# rpi-cc2538-uart.net
KiCad netlist of a schematic drawn in EAGLE
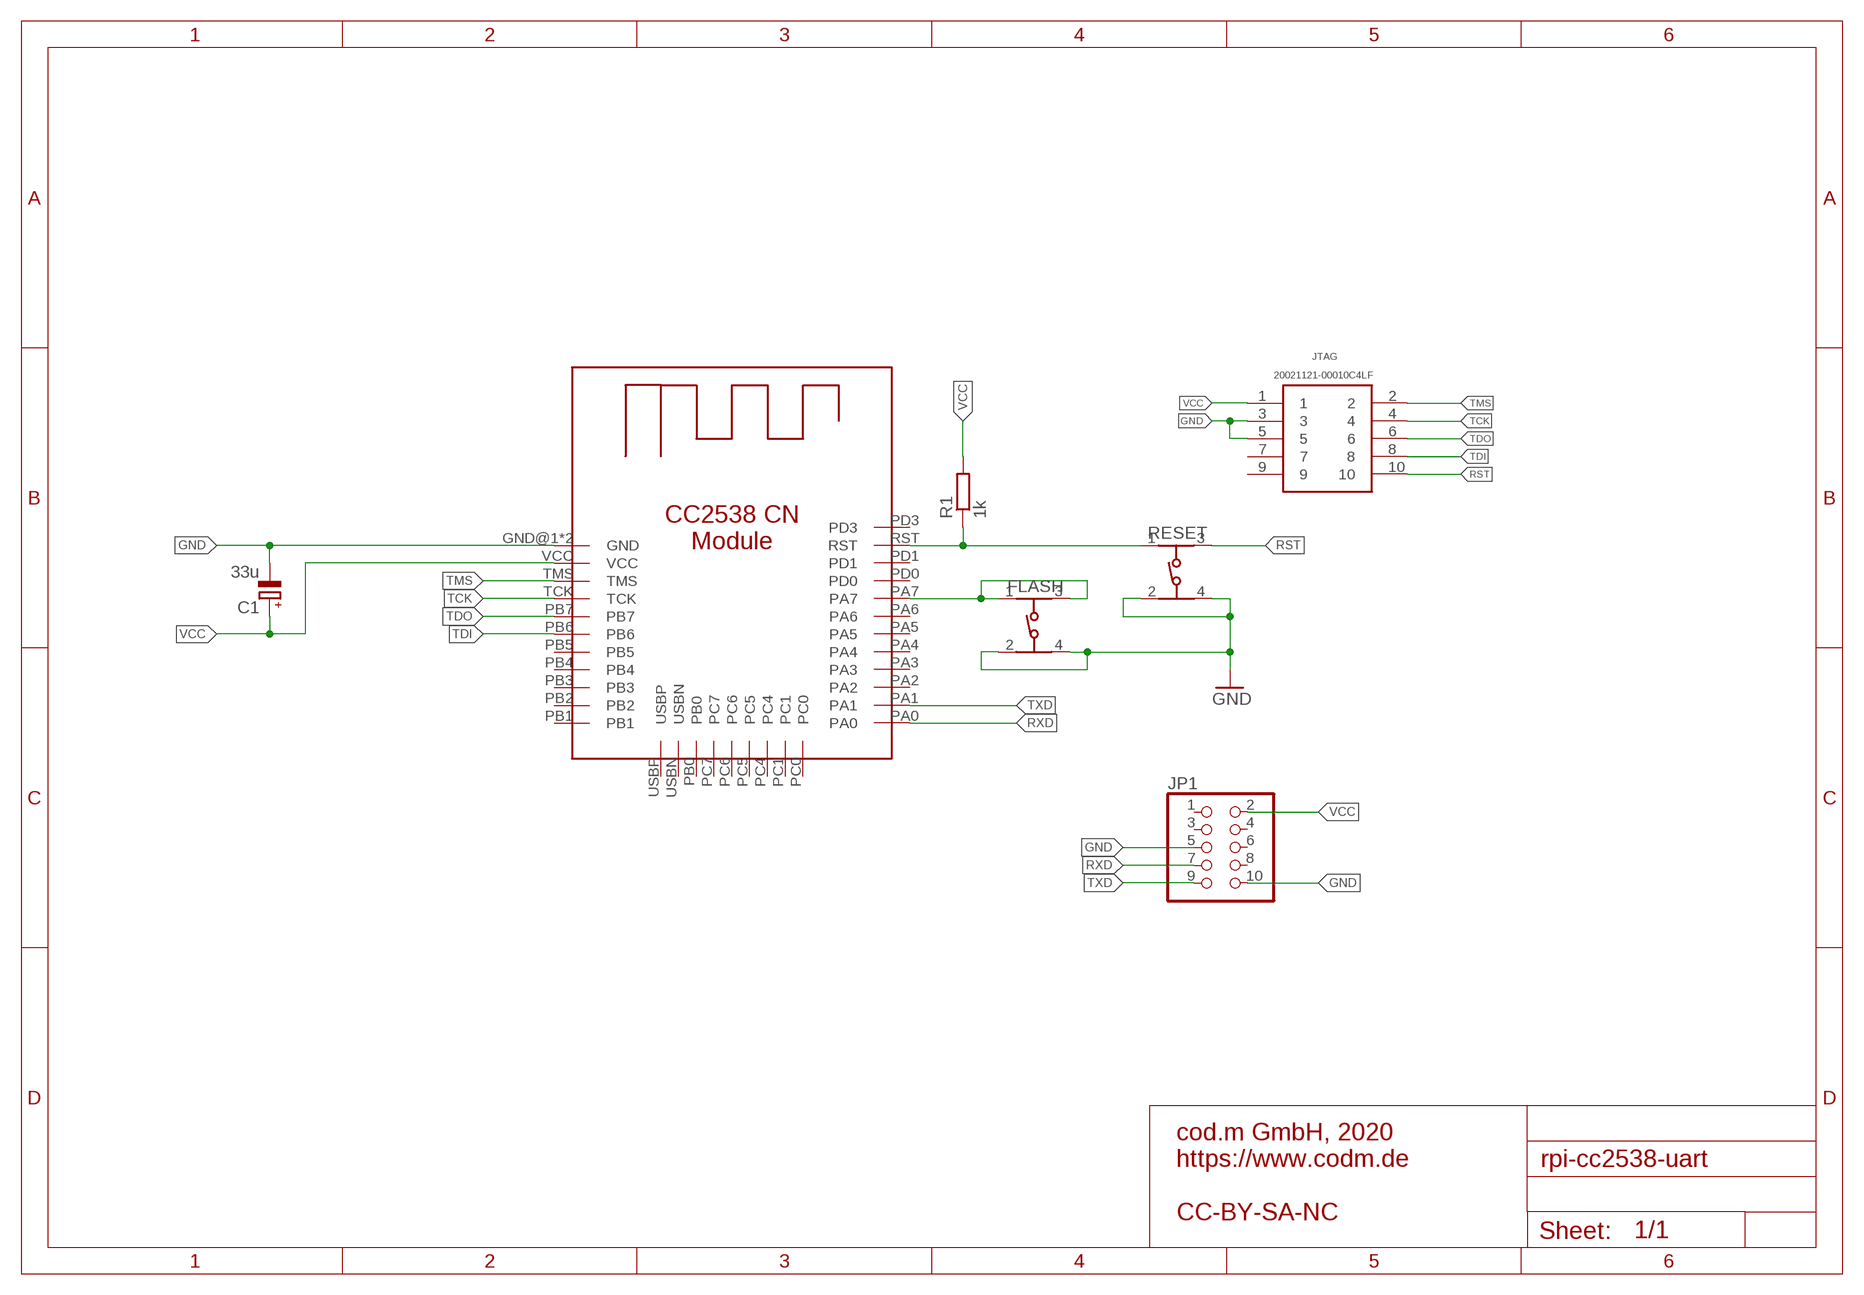
[diagram p0: schematic, sheet 1]

(export (version "E")
  (design (tool "Eeschema 10.0.6"))
  (components
    (comp (ref "C1")
      (value "33u")
      (footprint "eagle-import:A_3216-18W")
      (libsource (lib "eagle-import") (part "CPOL-EUA/3216-18W"))
    )
    (comp (ref "FLASH")
      (value "434153017835")
      (footprint "eagle-import:434153017835")
      (libsource (lib "eagle-import") (part "434153017835"))
    )
    (comp (ref "JP1")
      (value "PINHD-2X5")
      (footprint "eagle-import:2X05")
      (libsource (lib "eagle-import") (part "PINHD-2X5"))
    )
    (comp (ref "JTAG")
      (value "20021121-00010C4LF")
      (footprint "eagle-import:2002112100010C4LF")
      (fields (field (name "MOUSER_PART_NUMBER") "649-202112100010C4LF"))
      (libsource (lib "eagle-import") (part "20021121-00010C4LF"))
    )
    (comp (ref "R1")
      (value "1k")
      (footprint "eagle-import:R0805")
      (libsource (lib "eagle-import") (part "R-EU_R0805"))
    )
    (comp (ref "RESET")
      (value "434153017835")
      (footprint "eagle-import:434153017835")
      (libsource (lib "eagle-import") (part "434153017835"))
    )
    (comp (ref "U$1")
      (value "CC2538-CN")
      (footprint "eagle-import:CC2538-CN")
      (libsource (lib "eagle-import") (part "CC2538-CN"))
    )
  )
  (nets
    (net (code "1") (name "GND") (class "Default")
      (node (ref "C1") (pin "-") (pinfunction "-_-") (pintype "passive"))
      (node (ref "FLASH") (pin "2") (pinfunction "3_2") (pintype "passive"))
      (node (ref "FLASH") (pin "4") (pinfunction "4_4") (pintype "passive"))
      (node (ref "JP1") (pin "10") (pinfunction "10_10") (pintype "passive"))
      (node (ref "JP1") (pin "5") (pinfunction "5_5") (pintype "passive"))
      (node (ref "JTAG") (pin "3") (pinfunction "3_3") (pintype "bidirectional"))
      (node (ref "JTAG") (pin "5") (pinfunction "5_5") (pintype "bidirectional"))
      (node (ref "RESET") (pin "2") (pinfunction "3_2") (pintype "passive"))
      (node (ref "RESET") (pin "4") (pinfunction "4_4") (pintype "passive"))
      (node (ref "U$1") (pin "GND@1") (pinfunction "GND_GND@1") (pintype "bidirectional"))
      (node (ref "U$1") (pin "GND@2") (pinfunction "GND_GND@2") (pintype "bidirectional"))
    )
    (net (code "2") (name "Net-(FLASH-2)") (class "Default")
      (node (ref "FLASH") (pin "1") (pinfunction "1_1") (pintype "passive"))
      (node (ref "FLASH") (pin "3") (pinfunction "2_3") (pintype "passive"))
      (node (ref "U$1") (pin "PA7") (pinfunction "PA7_PA7") (pintype "bidirectional"))
    )
    (net (code "3") (name "RST") (class "Default")
      (node (ref "JTAG") (pin "10") (pinfunction "10_10") (pintype "bidirectional"))
      (node (ref "R1") (pin "1") (pinfunction "1_1") (pintype "passive"))
      (node (ref "RESET") (pin "1") (pinfunction "1_1") (pintype "passive"))
      (node (ref "RESET") (pin "3") (pinfunction "2_3") (pintype "passive"))
      (node (ref "U$1") (pin "RST") (pinfunction "RST_RST") (pintype "bidirectional"))
    )
    (net (code "4") (name "RXD") (class "Default")
      (node (ref "JP1") (pin "7") (pinfunction "7_7") (pintype "passive"))
      (node (ref "U$1") (pin "PA0") (pinfunction "PA0_PA0") (pintype "bidirectional"))
    )
    (net (code "5") (name "TCK") (class "Default")
      (node (ref "JTAG") (pin "4") (pinfunction "4_4") (pintype "bidirectional"))
      (node (ref "U$1") (pin "TCK") (pinfunction "TCK_TCK") (pintype "bidirectional"))
    )
    (net (code "6") (name "TDI") (class "Default")
      (node (ref "JTAG") (pin "8") (pinfunction "8_8") (pintype "bidirectional"))
      (node (ref "U$1") (pin "PB6") (pinfunction "PB6_PB6") (pintype "bidirectional"))
    )
    (net (code "7") (name "TDO") (class "Default")
      (node (ref "JTAG") (pin "6") (pinfunction "6_6") (pintype "bidirectional"))
      (node (ref "U$1") (pin "PB7") (pinfunction "PB7_PB7") (pintype "bidirectional"))
    )
    (net (code "8") (name "TMS") (class "Default")
      (node (ref "JTAG") (pin "2") (pinfunction "2_2") (pintype "bidirectional"))
      (node (ref "U$1") (pin "TMS") (pinfunction "TMS_TMS") (pintype "bidirectional"))
    )
    (net (code "9") (name "TXD") (class "Default")
      (node (ref "JP1") (pin "9") (pinfunction "9_9") (pintype "passive"))
      (node (ref "U$1") (pin "PA1") (pinfunction "PA1_PA1") (pintype "bidirectional"))
    )
    (net (code "10") (name "VCC") (class "Default")
      (node (ref "C1") (pin "+") (pinfunction "+_+") (pintype "passive"))
      (node (ref "JP1") (pin "2") (pinfunction "2_2") (pintype "passive"))
      (node (ref "JTAG") (pin "1") (pinfunction "1_1") (pintype "bidirectional"))
      (node (ref "R1") (pin "2") (pinfunction "2_2") (pintype "passive"))
      (node (ref "U$1") (pin "VCC") (pinfunction "VCC_VCC") (pintype "bidirectional"))
    )
    (net (code "11") (name "unconnected-(JP1-Pad1)") (class "Default")
      (node (ref "JP1") (pin "1") (pinfunction "1_1") (pintype "passive"))
    )
    (net (code "12") (name "unconnected-(JP1-Pad3)") (class "Default")
      (node (ref "JP1") (pin "3") (pinfunction "3_3") (pintype "passive"))
    )
    (net (code "13") (name "unconnected-(JP1-Pad4)") (class "Default")
      (node (ref "JP1") (pin "4") (pinfunction "4_4") (pintype "passive"))
    )
    (net (code "14") (name "unconnected-(JP1-Pad6)") (class "Default")
      (node (ref "JP1") (pin "6") (pinfunction "6_6") (pintype "passive"))
    )
    (net (code "15") (name "unconnected-(JP1-Pad8)") (class "Default")
      (node (ref "JP1") (pin "8") (pinfunction "8_8") (pintype "passive"))
    )
    (net (code "16") (name "unconnected-(JTAG-Pad7)") (class "Default")
      (node (ref "JTAG") (pin "7") (pinfunction "7_7") (pintype "bidirectional"))
    )
    (net (code "17") (name "unconnected-(JTAG-Pad9)") (class "Default")
      (node (ref "JTAG") (pin "9") (pinfunction "9_9") (pintype "bidirectional"))
    )
    (net (code "18") (name "unconnected-(U$1-PadPA2)") (class "Default")
      (node (ref "U$1") (pin "PA2") (pinfunction "PA2_PA2") (pintype "bidirectional"))
    )
    (net (code "19") (name "unconnected-(U$1-PadPA3)") (class "Default")
      (node (ref "U$1") (pin "PA3") (pinfunction "PA3_PA3") (pintype "bidirectional"))
    )
    (net (code "20") (name "unconnected-(U$1-PadPA4)") (class "Default")
      (node (ref "U$1") (pin "PA4") (pinfunction "PA4_PA4") (pintype "bidirectional"))
    )
    (net (code "21") (name "unconnected-(U$1-PadPA5)") (class "Default")
      (node (ref "U$1") (pin "PA5") (pinfunction "PA5_PA5") (pintype "bidirectional"))
    )
    (net (code "22") (name "unconnected-(U$1-PadPA6)") (class "Default")
      (node (ref "U$1") (pin "PA6") (pinfunction "PA6_PA6") (pintype "bidirectional"))
    )
    (net (code "23") (name "unconnected-(U$1-PadPB0)") (class "Default")
      (node (ref "U$1") (pin "PB0") (pinfunction "PB0_PB0") (pintype "bidirectional"))
    )
    (net (code "24") (name "unconnected-(U$1-PadPB1)") (class "Default")
      (node (ref "U$1") (pin "PB1") (pinfunction "PB1_PB1") (pintype "bidirectional"))
    )
    (net (code "25") (name "unconnected-(U$1-PadPB2)") (class "Default")
      (node (ref "U$1") (pin "PB2") (pinfunction "PB2_PB2") (pintype "bidirectional"))
    )
    (net (code "26") (name "unconnected-(U$1-PadPB3)") (class "Default")
      (node (ref "U$1") (pin "PB3") (pinfunction "PB3_PB3") (pintype "bidirectional"))
    )
    (net (code "27") (name "unconnected-(U$1-PadPB4)") (class "Default")
      (node (ref "U$1") (pin "PB4") (pinfunction "PB4_PB4") (pintype "bidirectional"))
    )
    (net (code "28") (name "unconnected-(U$1-PadPB5)") (class "Default")
      (node (ref "U$1") (pin "PB5") (pinfunction "PB5_PB5") (pintype "bidirectional"))
    )
    (net (code "29") (name "unconnected-(U$1-PadPC0)") (class "Default")
      (node (ref "U$1") (pin "PC0") (pinfunction "PC0_PC0") (pintype "bidirectional"))
    )
    (net (code "30") (name "unconnected-(U$1-PadPC1)") (class "Default")
      (node (ref "U$1") (pin "PC1") (pinfunction "PC1_PC1") (pintype "bidirectional"))
    )
    (net (code "31") (name "unconnected-(U$1-PadPC4)") (class "Default")
      (node (ref "U$1") (pin "PC4") (pinfunction "PC4_PC4") (pintype "bidirectional"))
    )
    (net (code "32") (name "unconnected-(U$1-PadPC5)") (class "Default")
      (node (ref "U$1") (pin "PC5") (pinfunction "PC5_PC5") (pintype "bidirectional"))
    )
    (net (code "33") (name "unconnected-(U$1-PadPC6)") (class "Default")
      (node (ref "U$1") (pin "PC6") (pinfunction "PC6_PC6") (pintype "bidirectional"))
    )
    (net (code "34") (name "unconnected-(U$1-PadPC7)") (class "Default")
      (node (ref "U$1") (pin "PC7") (pinfunction "PC7_PC7") (pintype "bidirectional"))
    )
    (net (code "35") (name "unconnected-(U$1-PadPD0)") (class "Default")
      (node (ref "U$1") (pin "PD0") (pinfunction "PD0_PD0") (pintype "bidirectional"))
    )
    (net (code "36") (name "unconnected-(U$1-PadPD1)") (class "Default")
      (node (ref "U$1") (pin "PD1") (pinfunction "PD1_PD1") (pintype "bidirectional"))
    )
    (net (code "37") (name "unconnected-(U$1-PadPD3)") (class "Default")
      (node (ref "U$1") (pin "PD3") (pinfunction "PD3_PD3") (pintype "bidirectional"))
    )
    (net (code "38") (name "unconnected-(U$1-PadUSBN)") (class "Default")
      (node (ref "U$1") (pin "USBN") (pinfunction "USBN_USBN") (pintype "bidirectional"))
    )
    (net (code "39") (name "unconnected-(U$1-PadUSBP)") (class "Default")
      (node (ref "U$1") (pin "USBP") (pinfunction "USBP_USBP") (pintype "bidirectional"))
    )
  )
)
